# DIOT_PSU_integrated.net
KiCad netlist of a schematic drawn in Altium Designer
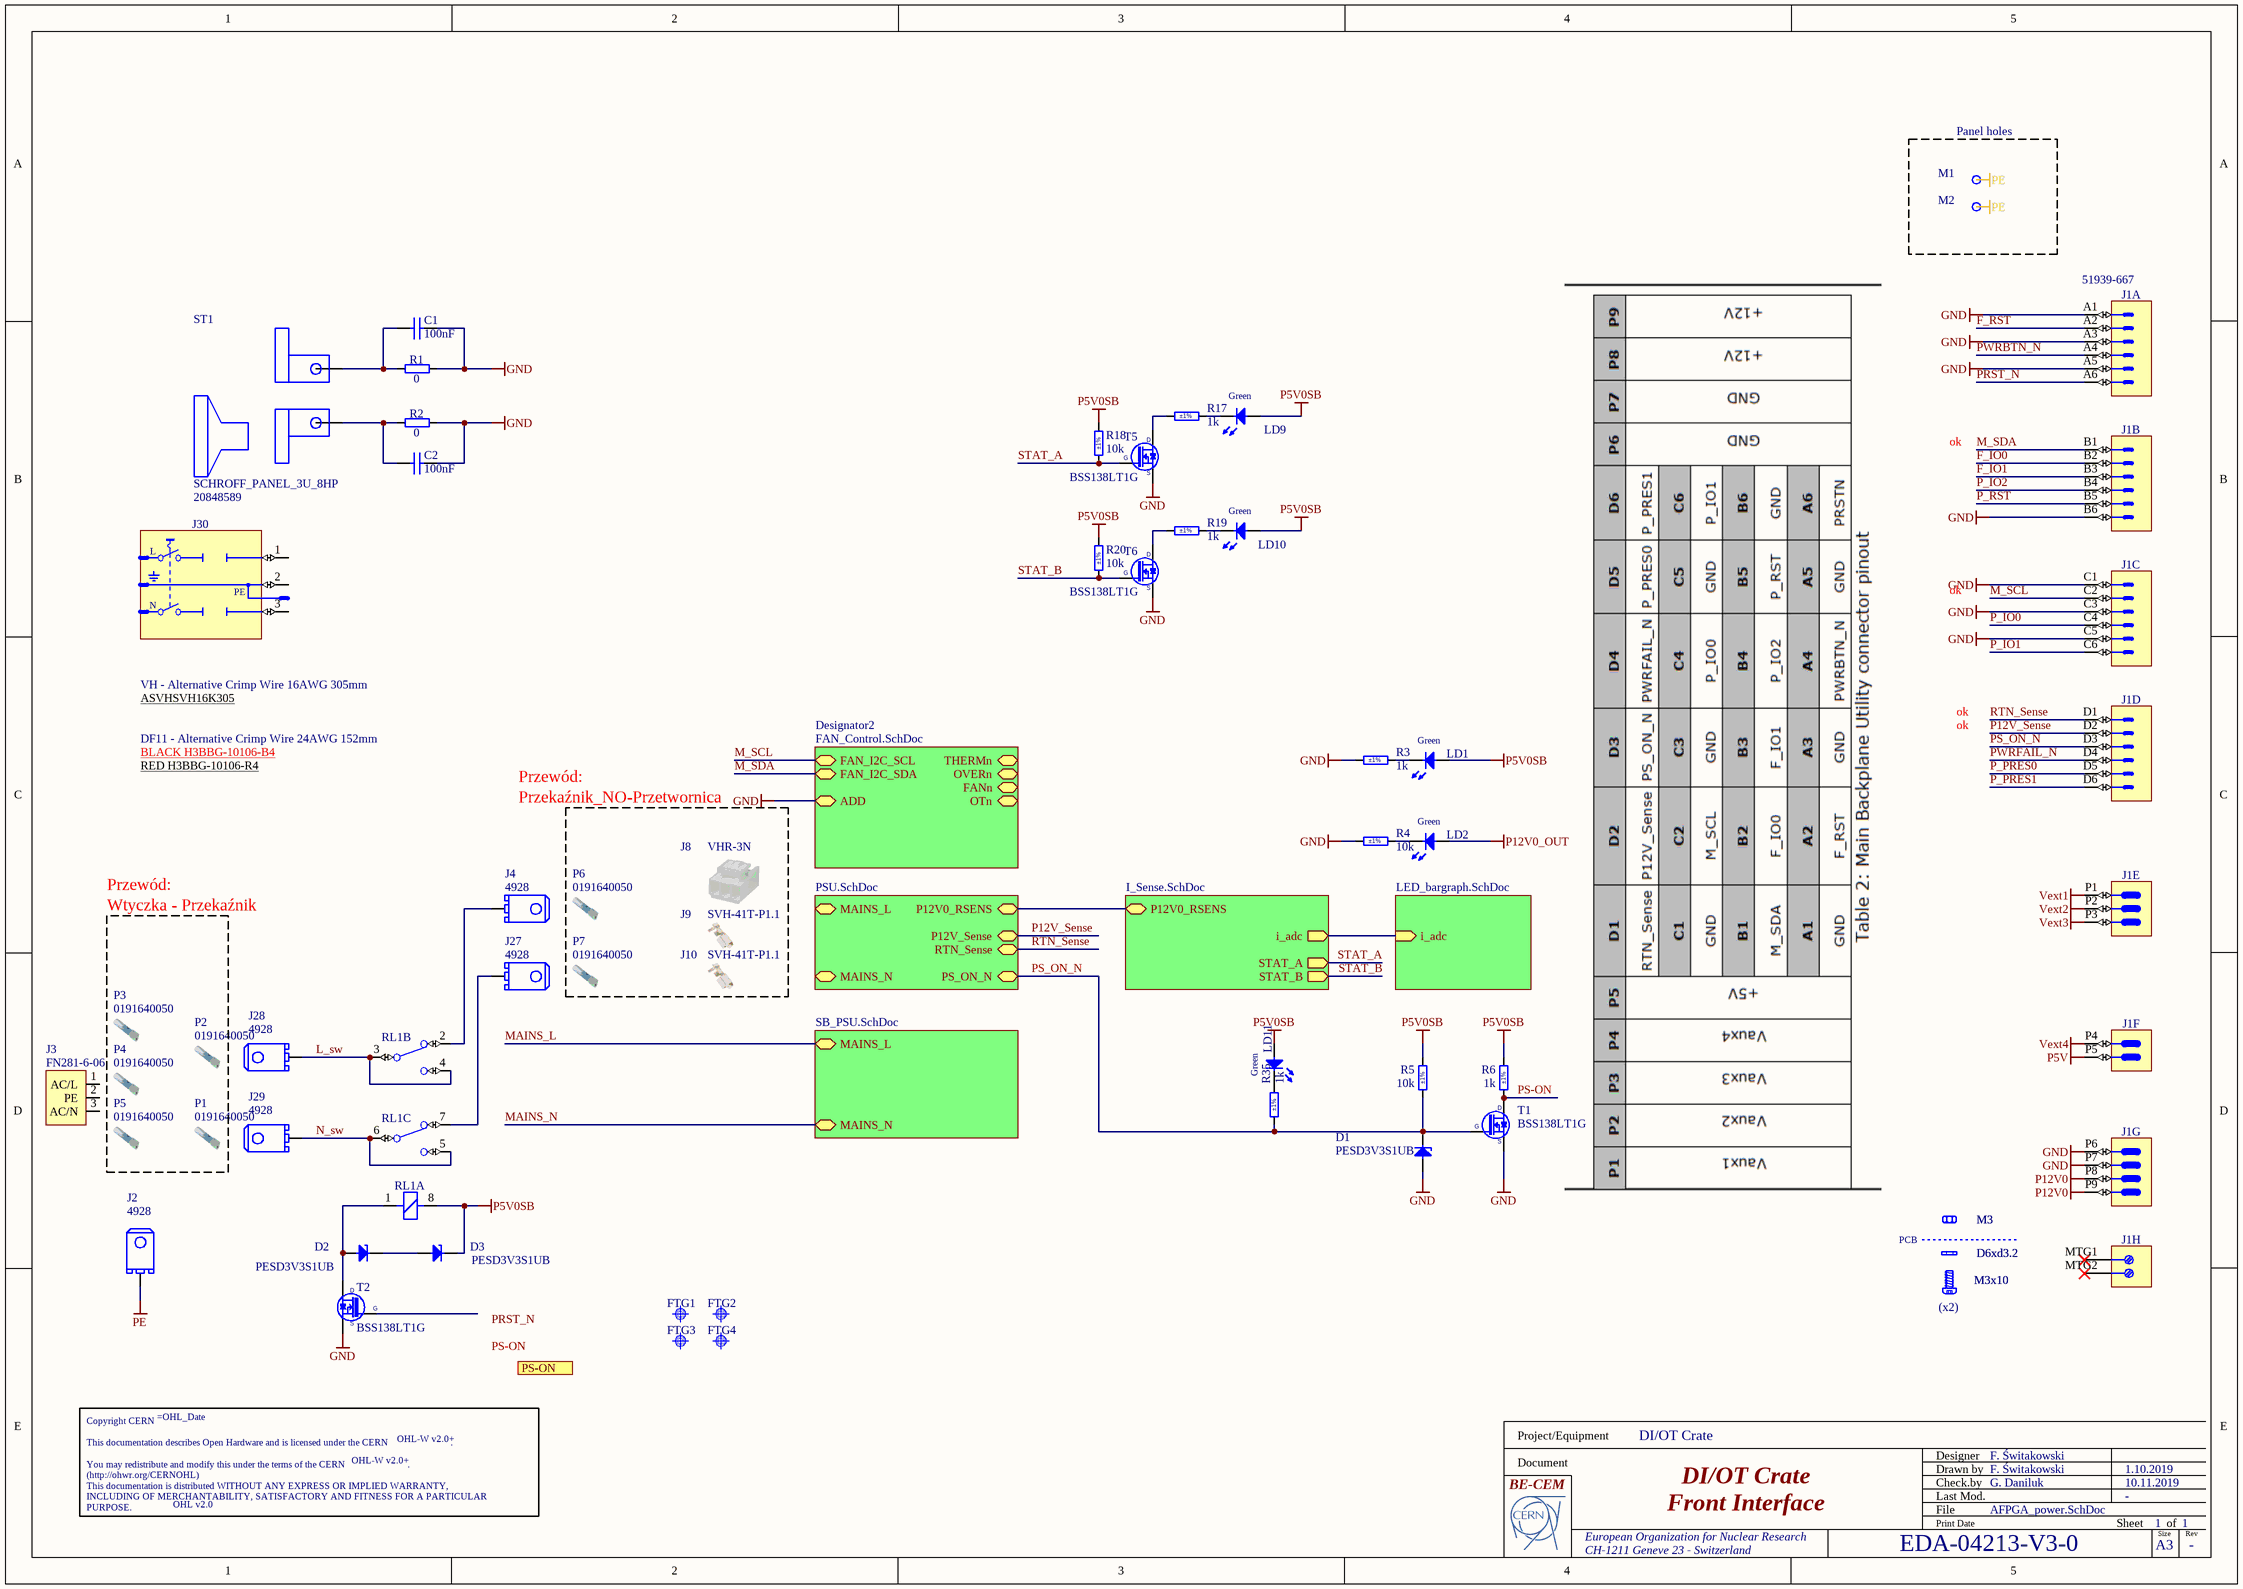
[diagram p0: DIOT_PSU_integrated.SchDoc]

(export (version "E")
  (design (tool "Eeschema 10.0.6"))
  (components
    (comp (ref "C1")
      (value "100nF")
      (footprint "CAPC1608X87N")
      (description "Non-polarised capacitor")
      (fields
        (field (name "PART NUMBER") "CC0603_100NF_50V_10%_X5R")
        (field (name "VOLTAGE") "50V")
        (field (name "AUTHOR") "CERN DEM MR")
      )
      (libsource (lib "Capacitors") (part "Capacitor - non polarized"))
    )
    (comp (ref "C2")
      (value "100nF")
      (footprint "CAPC1608X87N")
      (description "Non-polarised capacitor")
      (fields
        (field (name "PART NUMBER") "CC0603_100NF_50V_10%_X5R")
        (field (name "VOLTAGE") "50V")
        (field (name "AUTHOR") "CERN DEM MR")
      )
      (libsource (lib "Capacitors") (part "Capacitor - non polarized"))
    )
    (comp (ref "D1")
      (value "PESD3V3S1UB")
      (footprint "SODFL1608X65N")
      (description "ESD protection diode")
      (fields
        (field (name "VOLTAGE") "3V3")
        (field (name "POWER") "330W")
        (field (name "AUTHOR") "CERN DEM JLC")
      )
      (libsource (lib "ICs And Semiconductors") (part "Diode ESD"))
    )
    (comp (ref "D2")
      (value "PESD3V3S1UB")
      (footprint "SODFL1608X65N")
      (description "ESD protection diode")
      (fields
        (field (name "VOLTAGE") "3V3")
        (field (name "POWER") "330W")
        (field (name "AUTHOR") "CERN DEM JLC")
      )
      (libsource (lib "ICs And Semiconductors") (part "Diode ESD"))
    )
    (comp (ref "D3")
      (value "PESD3V3S1UB")
      (footprint "SODFL1608X65N")
      (description "ESD protection diode")
      (fields
        (field (name "VOLTAGE") "3V3")
        (field (name "POWER") "330W")
        (field (name "AUTHOR") "CERN DEM JLC")
      )
      (libsource (lib "ICs And Semiconductors") (part "Diode ESD"))
    )
    (comp (ref "FTG1")
      (value "Use only in PCB")
      (footprint "FIDUCIAL_TOP_C100-200")
      (description "Fiducial Target")
      (fields (field (name "PART NUMBER") "FIDUCIAL_TARGET_C100-200") (field (name "AUTHOR") "CERN DEM JLC"))
      (libsource (lib "Eletro-mechanical") (part "Fiducial Target"))
    )
    (comp (ref "FTG2")
      (value "Use only in PCB")
      (footprint "FIDUCIAL_TOP_S100-200")
      (description "Fiducial Target")
      (fields (field (name "PART NUMBER") "FIDUCIAL_TARGET_S100-200") (field (name "AUTHOR") "CERN DEM JLC"))
      (libsource (lib "Eletro-mechanical") (part "Fiducial Target"))
    )
    (comp (ref "FTG3")
      (value "Use only in PCB")
      (footprint "FIDUCIAL_TOP_C100-200")
      (description "Fiducial Target")
      (fields (field (name "PART NUMBER") "FIDUCIAL_TARGET_C100-200") (field (name "AUTHOR") "CERN DEM JLC"))
      (libsource (lib "Eletro-mechanical") (part "Fiducial Target"))
    )
    (comp (ref "FTG4")
      (value "Use only in PCB")
      (footprint "FIDUCIAL_TOP_S100-200")
      (description "Fiducial Target")
      (fields (field (name "PART NUMBER") "FIDUCIAL_TARGET_S100-200") (field (name "AUTHOR") "CERN DEM JLC"))
      (libsource (lib "Eletro-mechanical") (part "Fiducial Target"))
    )
    (comp (ref "J1")
      (value "PwrBlade")
      (footprint "AMPHENOL_51939-667")
      (description "Thru-Hole, Lead 3.43mm, PowerBlade Right Angled Power Connector 3ACP 2P 24S 4P Contacts")
      (fields
        (field (name "PART NUMBER") "AMPHENOL_51939-667")
        (field (name "MANUFACTURER") "AMPHENOL")
        (field (name "MANUFACTURER PART NUMBER") "51939-667")
        (field (name "AUTHOR") "CERN DEM JLC")
      )
      (libsource (lib "Connectors") (part "AMPHENOL_51939-667"))
    )
    (comp (ref "J2")
      (value "4928")
      (footprint "KEYSTONE_4928")
      (description "0.240\" (6.10mm) Quick Connect Male Solder Connector Non-Insulated")
      (fields (field (name "MANUFACTURER") "KEYSTONE") (field (name "AUTHOR") "LPA"))
      (libsource (lib "DIOT_PSU_integrated") (part "KEYSTONE_4928"))
    )
    (comp (ref "J3")
      (value "FN281-6-06")
      (footprint "FN9264-2-06")
      (description "Power Entry Connector Receptacle, Male Blades - Module IEC 320-C14 Panel Mount, Flange")
      (fields (field (name "MANUFACTURER") "Schaffner EMC Inc.") (field (name "AUTHOR") "LPA"))
      (libsource (lib "DIOT_PSU_integrated") (part "FN281-6-06"))
    )
    (comp (ref "J4")
      (value "4928")
      (footprint "KEYSTONE_4928")
      (description "0.240\" (6.10mm) Quick Connect Male Solder Connector Non-Insulated")
      (fields (field (name "MANUFACTURER") "KEYSTONE") (field (name "AUTHOR") "LPA"))
      (libsource (lib "DIOT_PSU_integrated") (part "KEYSTONE_4928"))
    )
    (comp (ref "J8")
      (value "VHR-3N")
      (footprint "VHR-3N")
      (description "3 Rectangular Connectors - Housings Receptacle Natural 0.156\" (3.96mm)")
      (fields (field (name "MANUFACTURER") "JST Sales America Inc.") (field (name "AUTHOR") "LPA"))
      (libsource (lib "EDA-04213-V3-0_project") (part "VHR-3N"))
    )
    (comp (ref "J9")
      (value "SVH-41T-P1.1")
      (footprint "SVH-41T-P1.1")
      (description "Socket Contact Tin 16-20 AWG Crimp")
      (fields (field (name "MANUFACTURER") "JST Sales America Inc.") (field (name "AUTHOR") "LPA"))
      (libsource (lib "EDA-04213-V3-0_project") (part "SVH-41T-P1.1"))
    )
    (comp (ref "J10")
      (value "SVH-41T-P1.1")
      (footprint "SVH-41T-P1.1")
      (description "Socket Contact Tin 16-20 AWG Crimp")
      (fields (field (name "MANUFACTURER") "JST Sales America Inc.") (field (name "AUTHOR") "LPA"))
      (libsource (lib "EDA-04213-V3-0_project") (part "SVH-41T-P1.1"))
    )
    (comp (ref "J27")
      (value "4928")
      (footprint "KEYSTONE_4928")
      (description "0.240\" (6.10mm) Quick Connect Male Solder Connector Non-Insulated")
      (fields (field (name "MANUFACTURER") "KEYSTONE") (field (name "AUTHOR") "LPA"))
      (libsource (lib "DIOT_PSU_integrated") (part "KEYSTONE_4928"))
    )
    (comp (ref "J28")
      (value "4928")
      (footprint "KEYSTONE_4928")
      (description "0.240\" (6.10mm) Quick Connect Male Solder Connector Non-Insulated")
      (fields (field (name "MANUFACTURER") "KEYSTONE") (field (name "AUTHOR") "LPA"))
      (libsource (lib "DIOT_PSU_integrated") (part "KEYSTONE_4928"))
    )
    (comp (ref "J29")
      (value "4928")
      (footprint "KEYSTONE_4928")
      (description "0.240\" (6.10mm) Quick Connect Male Solder Connector Non-Insulated")
      (fields (field (name "MANUFACTURER") "KEYSTONE") (field (name "AUTHOR") "LPA"))
      (libsource (lib "DIOT_PSU_integrated") (part "KEYSTONE_4928"))
    )
    (comp (ref "J30")
      (value "IEC")
      (footprint "SCHURTER_DD21.0121.1111")
      (description "Connector 3 Male 2P+ 2 Fuse Holder + Line Switch 2 Poles")
      (fields
        (field (name "PART NUMBER") "SCHURTER_DD21.0121.1111")
        (field (name "MANUFACTURER") "SCHURTER")
        (field (name "AUTHOR") "CERN DEM JLC")
      )
      (libsource (lib "Connectors") (part "Connector 3 Male 2P+T+2FUSH+SW2P"))
    )
    (comp (ref "LD1")
      (value "Green")
      (footprint "LED_AVAGO_HSME-C120")
      (description "LED Green 1C 2A")
      (fields
        (field (name "PART NUMBER") "LED_AVAGO_HSME-C120")
        (field (name "MANUFACTURER") "AVAGO TECHNOLOGIES")
        (field (name "AUTHOR") "CERN DEM JMW")
      )
      (libsource (lib "ICs And Semiconductors") (part "LED Green 1C 2A"))
    )
    (comp (ref "LD2")
      (value "Green")
      (footprint "LED_AVAGO_HSME-C120")
      (description "LED Green 1C 2A")
      (fields
        (field (name "PART NUMBER") "LED_AVAGO_HSME-C120")
        (field (name "MANUFACTURER") "AVAGO TECHNOLOGIES")
        (field (name "AUTHOR") "CERN DEM JMW")
      )
      (libsource (lib "ICs And Semiconductors") (part "LED Green 1C 2A"))
    )
    (comp (ref "LD9")
      (value "Green")
      (footprint "LED_AVAGO_HSME-C120")
      (description "LED Green 1C 2A")
      (fields
        (field (name "PART NUMBER") "LED_AVAGO_HSME-C120")
        (field (name "MANUFACTURER") "AVAGO TECHNOLOGIES")
        (field (name "AUTHOR") "CERN DEM JMW")
      )
      (libsource (lib "ICs And Semiconductors") (part "LED Green 1C 2A"))
    )
    (comp (ref "LD10")
      (value "Green")
      (footprint "LED_AVAGO_HSME-C120")
      (description "LED Green 1C 2A")
      (fields
        (field (name "PART NUMBER") "LED_AVAGO_HSME-C120")
        (field (name "MANUFACTURER") "AVAGO TECHNOLOGIES")
        (field (name "AUTHOR") "CERN DEM JMW")
      )
      (libsource (lib "ICs And Semiconductors") (part "LED Green 1C 2A"))
    )
    (comp (ref "LD11")
      (value "Green")
      (footprint "LED_AVAGO_HSME-C120")
      (description "LED Green 1C 2A")
      (fields
        (field (name "PART NUMBER") "LED_AVAGO_HSME-C120")
        (field (name "MANUFACTURER") "AVAGO TECHNOLOGIES")
        (field (name "AUTHOR") "CERN DEM JMW")
      )
      (libsource (lib "ICs And Semiconductors") (part "LED Green 1C 2A"))
    )
    (comp (ref "M1")
      (value "Plated Hole")
      (footprint "MTG300_600")
      (description "Single Terminal Socket")
      (fields (field (name "PART NUMBER") "PLATED_HOLE3.0_PAD6.0") (field (name "AUTHOR") "CERN DEM JLC"))
      (libsource (lib "Eletro-mechanical") (part "Single Terminal Socket"))
    )
    (comp (ref "M2")
      (value "Plated Hole")
      (footprint "MTG300_600")
      (description "Single Terminal Socket")
      (fields (field (name "PART NUMBER") "PLATED_HOLE3.0_PAD6.0") (field (name "AUTHOR") "CERN DEM JLC"))
      (libsource (lib "Eletro-mechanical") (part "Single Terminal Socket"))
    )
    (comp (ref "NUT1")
      (value "M3")
      (footprint "BOSSARD_BN628-1241443_v")
      (description "Nut")
      (fields
        (field (name "PART NUMBER") "BOSSARD_BN628-1241443_v")
        (field (name "MANUFACTURER") "BOSSARD")
        (field (name "AUTHOR") "CERN DEM JMW")
      )
      (libsource (lib "Eletro-mechanical") (part "Nut"))
    )
    (comp (ref "NUT2")
      (value "M3")
      (footprint "BOSSARD_BN628-1241443_v")
      (description "Nut")
      (fields
        (field (name "PART NUMBER") "BOSSARD_BN628-1241443_v")
        (field (name "MANUFACTURER") "BOSSARD")
        (field (name "AUTHOR") "CERN DEM JMW")
      )
      (libsource (lib "Eletro-mechanical") (part "Nut"))
    )
    (comp (ref "OHL1")
      (value "CERN_OHL")
      (footprint "CERN_OHL")
      (fields (field (name "AUTHOR") "CERN DEM HF"))
      (libsource (lib "Eletro-mechanical") (part "CERN_OHL"))
    )
    (comp (ref "P1")
      (value "0191640050")
      (footprint "0191640050")
      (description "0.250\" (6.35mm) Quick Connect Female 14-16 AWG Crimp Connector Fully Insulated Heat Shrink")
      (fields (field (name "MANUFACTURER") "Molex") (field (name "AUTHOR") "LPA"))
      (libsource (lib "EDA-04213-V3-0_project") (part "0191640050"))
    )
    (comp (ref "P2")
      (value "0191640050")
      (footprint "0191640050")
      (description "0.250\" (6.35mm) Quick Connect Female 14-16 AWG Crimp Connector Fully Insulated Heat Shrink")
      (fields (field (name "MANUFACTURER") "Molex") (field (name "AUTHOR") "LPA"))
      (libsource (lib "EDA-04213-V3-0_project") (part "0191640050"))
    )
    (comp (ref "P3")
      (value "0191640050")
      (footprint "0191640050")
      (description "0.250\" (6.35mm) Quick Connect Female 14-16 AWG Crimp Connector Fully Insulated Heat Shrink")
      (fields (field (name "MANUFACTURER") "Molex") (field (name "AUTHOR") "LPA"))
      (libsource (lib "EDA-04213-V3-0_project") (part "0191640050"))
    )
    (comp (ref "P4")
      (value "0191640050")
      (footprint "0191640050")
      (description "0.250\" (6.35mm) Quick Connect Female 14-16 AWG Crimp Connector Fully Insulated Heat Shrink")
      (fields (field (name "MANUFACTURER") "Molex") (field (name "AUTHOR") "LPA"))
      (libsource (lib "EDA-04213-V3-0_project") (part "0191640050"))
    )
    (comp (ref "P5")
      (value "0191640050")
      (footprint "0191640050")
      (description "0.250\" (6.35mm) Quick Connect Female 14-16 AWG Crimp Connector Fully Insulated Heat Shrink")
      (fields (field (name "MANUFACTURER") "Molex") (field (name "AUTHOR") "LPA"))
      (libsource (lib "EDA-04213-V3-0_project") (part "0191640050"))
    )
    (comp (ref "P6")
      (value "0191640050")
      (footprint "0191640050")
      (description "0.250\" (6.35mm) Quick Connect Female 14-16 AWG Crimp Connector Fully Insulated Heat Shrink")
      (fields (field (name "MANUFACTURER") "Molex") (field (name "AUTHOR") "LPA"))
      (libsource (lib "EDA-04213-V3-0_project") (part "0191640050"))
    )
    (comp (ref "P7")
      (value "0191640050")
      (footprint "0191640050")
      (description "0.250\" (6.35mm) Quick Connect Female 14-16 AWG Crimp Connector Fully Insulated Heat Shrink")
      (fields (field (name "MANUFACTURER") "Molex") (field (name "AUTHOR") "LPA"))
      (libsource (lib "EDA-04213-V3-0_project") (part "0191640050"))
    )
    (comp (ref "R1")
      (value "0")
      (footprint "RESC1608X55N")
      (description "Resistor")
      (fields
        (field (name "PART NUMBER") "R0603_0R_JUMPER")
        (field (name "MANUFACTURER") "GENERIC")
        (field (name "AUTHOR") "CERN DEM JLC")
      )
      (libsource (lib "Resistors") (part "Resistor"))
    )
    (comp (ref "R2")
      (value "0")
      (footprint "RESC1608X55N")
      (description "Resistor")
      (fields
        (field (name "PART NUMBER") "R0603_0R_JUMPER")
        (field (name "MANUFACTURER") "GENERIC")
        (field (name "AUTHOR") "CERN DEM JLC")
      )
      (libsource (lib "Resistors") (part "Resistor"))
    )
    (comp (ref "R3")
      (value "1k")
      (footprint "RESC1608X55N")
      (description "Resistor - 1%")
      (fields
        (field (name "TOLERANCE") "±1%")
        (field (name "PART NUMBER") "R0603_1K_1%_0.1W_100PPM")
        (field (name "POWER") "0.1W")
        (field (name "AUTHOR") "CERN DEM JLC")
      )
      (libsource (lib "Resistors") (part "Resistor - 1%"))
    )
    (comp (ref "R4")
      (value "10k")
      (footprint "RESC1608X55N")
      (description "Resistor - 1%")
      (fields
        (field (name "TOLERANCE") "±1%")
        (field (name "PART NUMBER") "R0603_10K_1%_0.1W_100PPM")
        (field (name "POWER") "0.1W")
        (field (name "AUTHOR") "CERN DEM JLC")
      )
      (libsource (lib "Resistors") (part "Resistor - 1%"))
    )
    (comp (ref "R5")
      (value "10k")
      (footprint "RESC1608X55N")
      (description "Resistor - 1%")
      (fields
        (field (name "TOLERANCE") "±1%")
        (field (name "PART NUMBER") "R0603_10K_1%_0.1W_100PPM")
        (field (name "POWER") "0.1W")
        (field (name "AUTHOR") "CERN DEM JLC")
      )
      (libsource (lib "Resistors") (part "Resistor - 1%"))
    )
    (comp (ref "R6")
      (value "1k")
      (footprint "RESC1608X55N")
      (description "Resistor - 1%")
      (fields
        (field (name "TOLERANCE") "±1%")
        (field (name "PART NUMBER") "R0603_1K_1%_0.1W_100PPM")
        (field (name "POWER") "0.1W")
        (field (name "AUTHOR") "CERN DEM JLC")
      )
      (libsource (lib "Resistors") (part "Resistor - 1%"))
    )
    (comp (ref "R17")
      (value "1k")
      (footprint "RESC1608X55N")
      (description "Resistor - 1%")
      (fields
        (field (name "TOLERANCE") "±1%")
        (field (name "PART NUMBER") "R0603_1K_1%_0.1W_100PPM")
        (field (name "POWER") "0.1W")
        (field (name "AUTHOR") "CERN DEM JLC")
      )
      (libsource (lib "Resistors") (part "Resistor - 1%"))
    )
    (comp (ref "R18")
      (value "10k")
      (footprint "RESC1608X55N")
      (description "Resistor - 1%")
      (fields
        (field (name "TOLERANCE") "±1%")
        (field (name "PART NUMBER") "R0603_10K_1%_0.1W_100PPM")
        (field (name "POWER") "0.1W")
        (field (name "AUTHOR") "CERN DEM JLC")
      )
      (libsource (lib "Resistors") (part "Resistor - 1%"))
    )
    (comp (ref "R19")
      (value "1k")
      (footprint "RESC1608X55N")
      (description "Resistor - 1%")
      (fields
        (field (name "TOLERANCE") "±1%")
        (field (name "PART NUMBER") "R0603_1K_1%_0.1W_100PPM")
        (field (name "POWER") "0.1W")
        (field (name "AUTHOR") "CERN DEM JLC")
      )
      (libsource (lib "Resistors") (part "Resistor - 1%"))
    )
    (comp (ref "R20")
      (value "10k")
      (footprint "RESC1608X55N")
      (description "Resistor - 1%")
      (fields
        (field (name "TOLERANCE") "±1%")
        (field (name "PART NUMBER") "R0603_10K_1%_0.1W_100PPM")
        (field (name "POWER") "0.1W")
        (field (name "AUTHOR") "CERN DEM JLC")
      )
      (libsource (lib "Resistors") (part "Resistor - 1%"))
    )
    (comp (ref "R35")
      (value "1k")
      (footprint "RESC1608X55N")
      (description "Resistor - 1%")
      (fields
        (field (name "TOLERANCE") "±1%")
        (field (name "PART NUMBER") "R0603_1K_1%_0.1W_100PPM")
        (field (name "POWER") "0.1W")
        (field (name "AUTHOR") "CERN DEM JLC")
      )
      (libsource (lib "Resistors") (part "Resistor - 1%"))
    )
    (comp (ref "RL1")
      (value "REL_OMRON_G2RL-24")
      (footprint "REL_OMRON_G2RL-24")
      (description "DPDT Power Relay, G2RL Series")
      (fields
        (field (name "PART NUMBER") "REL_OMRON_G2RL-24-DC5")
        (field (name "MANUFACTURER") "OMRON ELECTRONIC")
        (field (name "AUTHOR") "CERN DEM BC")
      )
      (libsource (lib "Eletro-mechanical") (part "REL_OMRON_G2RL-24"))
    )
    (comp (ref "SCREW1")
      (value "M3x10")
      (footprint "BOSSARD_BN5687-3061608_v")
      (description "Screw")
      (fields
        (field (name "PART NUMBER") "BOSSARD_BN5687-3061608_v")
        (field (name "MANUFACTURER") "BOSSARD")
        (field (name "AUTHOR") "CERN DEM JLC")
      )
      (libsource (lib "Eletro-mechanical") (part "Screw"))
    )
    (comp (ref "SCREW2")
      (value "M3x10")
      (footprint "BOSSARD_BN5687-3061608_v")
      (description "Screw")
      (fields
        (field (name "PART NUMBER") "BOSSARD_BN5687-3061608_v")
        (field (name "MANUFACTURER") "BOSSARD")
        (field (name "AUTHOR") "CERN DEM JLC")
      )
      (libsource (lib "Eletro-mechanical") (part "Screw"))
    )
    (comp (ref "ST1")
      (value "SCHROFF_PANEL_3U_8HP")
      (footprint "SCHROFF_PANEL_3HP_8U_CPCIS_AC_PSU")
      (description "Schroff 8HP 4U EUROCARD Panel with ejector")
      (fields
        (field (name "MANUFACTURER") "Schroff")
        (field (name "MANUFACTURER PART NUMBER") "20848589")
        (field (name "MANUFACTURER PART NUMBER 2") "20848589")
      )
      (libsource (lib "DIOT_PSU_integrated") (part "SCHROFF_PANEL_3U_8HP_CPCIS_PSU"))
    )
    (comp (ref "T1")
      (value "BSS138LT1G")
      (footprint "SOT95P240X110-3N")
      (description "N-CHANNEL MOSFET WITH DIODE")
      (fields
        (field (name "MANUFACTURER") "ON SEMICONDUCTOR")
        (field (name "MANUFACTURER PART NUMBER") "BSS138L")
        (field (name "AUTHOR") "CERN DEM JLC")
      )
      (libsource (lib "ICs And Semiconductors") (part "N-MOSFET-D 1G 2S 3D"))
    )
    (comp (ref "T2")
      (value "BSS138LT1G")
      (footprint "SOT95P240X110-3N")
      (description "N-CHANNEL MOSFET WITH DIODE")
      (fields
        (field (name "MANUFACTURER") "ON SEMICONDUCTOR")
        (field (name "MANUFACTURER PART NUMBER") "BSS138L")
        (field (name "AUTHOR") "CERN DEM JLC")
      )
      (libsource (lib "") (part "N-MOSFET-D 1G 2S 3D_1"))
    )
    (comp (ref "T5")
      (value "BSS138LT1G")
      (footprint "SOT95P240X110-3N")
      (description "N-CHANNEL MOSFET WITH DIODE")
      (fields (field (name "MANUFACTURER") "ON SEMICONDUCTOR") (field (name "AUTHOR") "CERN DEM JLC"))
      (libsource (lib "ICs And Semiconductors") (part "N-MOSFET-D 1G 2S 3D"))
    )
    (comp (ref "T6")
      (value "BSS138LT1G")
      (footprint "SOT95P240X110-3N")
      (description "N-CHANNEL MOSFET WITH DIODE")
      (fields (field (name "MANUFACTURER") "ON SEMICONDUCTOR") (field (name "AUTHOR") "CERN DEM JLC"))
      (libsource (lib "ICs And Semiconductors") (part "N-MOSFET-D 1G 2S 3D"))
    )
    (comp (ref "WASHER1")
      (value "D6xd3.2")
      (footprint "BOSSARD_BN83728-8243964_v")
      (description "Washer")
      (fields
        (field (name "PART NUMBER") "BOSSARD_BN83728-8243964_v")
        (field (name "MANUFACTURER") "BOSSARD")
        (field (name "AUTHOR") "CERN DEM JLC")
      )
      (libsource (lib "Eletro-mechanical") (part "Washer"))
    )
    (comp (ref "WASHER2")
      (value "D6xd3.2")
      (footprint "BOSSARD_BN83728-8243964_v")
      (description "Washer")
      (fields
        (field (name "PART NUMBER") "BOSSARD_BN83728-8243964_v")
        (field (name "MANUFACTURER") "BOSSARD")
        (field (name "AUTHOR") "CERN DEM JLC")
      )
      (libsource (lib "Eletro-mechanical") (part "Washer"))
    )
  )
  (nets
    (net (code "2") (name "/F_IO0") (class "Default")
      (node (ref "J1") (pin "B2") (pinfunction "B2_B2") (pintype "bidirectional"))
    )
    (net (code "3") (name "/F_IO1") (class "Default")
      (node (ref "J1") (pin "B3") (pinfunction "B3_B3") (pintype "bidirectional"))
    )
    (net (code "4") (name "/F_RST") (class "Default")
      (node (ref "J1") (pin "A2") (pinfunction "A2_A2") (pintype "bidirectional"))
    )
    (net (code "5") (name "/L_sw") (class "Default")
      (node (ref "J28") (pin "1") (pinfunction "1_1") (pintype "passive"))
      (node (ref "RL1") (pin "3") (pinfunction "C_3") (pintype "bidirectional"))
      (node (ref "RL1") (pin "4") (pinfunction "NO_4") (pintype "bidirectional"))
    )
    (net (code "10") (name "/M_SCL") (class "Default")
      (node (ref "J1") (pin "C2") (pinfunction "C2_C2") (pintype "bidirectional"))
    )
    (net (code "11") (name "/M_SDA") (class "Default")
      (node (ref "J1") (pin "B1") (pinfunction "B1_B1") (pintype "bidirectional"))
    )
    (net (code "12") (name "/N_sw") (class "Default")
      (node (ref "J29") (pin "1") (pinfunction "1_1") (pintype "passive"))
      (node (ref "RL1") (pin "5") (pinfunction "NO_5") (pintype "bidirectional"))
      (node (ref "RL1") (pin "6") (pinfunction "C_6") (pintype "bidirectional"))
    )
    (net (code "16") (name "/P12V_Sense") (class "Default")
      (node (ref "J1") (pin "D2") (pinfunction "D2_D2") (pintype "bidirectional"))
    )
    (net (code "17") (name "/PRST_N") (class "Default")
      (node (ref "J1") (pin "A6") (pinfunction "A6_A6") (pintype "bidirectional"))
    )
    (net (code "18") (name "/PS-ON") (class "Default")
      (node (ref "R6") (pin "1") (pinfunction "1_1") (pintype "passive"))
      (node (ref "T1") (pin "3") (pinfunction "D_3") (pintype "passive"))
    )
    (net (code "19") (name "/PS_ON_N") (class "Default")
      (node (ref "D1") (pin "1") (pinfunction "C_1") (pintype "passive"))
      (node (ref "J1") (pin "D3") (pinfunction "D3_D3") (pintype "bidirectional"))
      (node (ref "R35") (pin "1") (pinfunction "1_1") (pintype "passive"))
      (node (ref "R5") (pin "1") (pinfunction "1_1") (pintype "passive"))
      (node (ref "T1") (pin "1") (pinfunction "G_1") (pintype "passive"))
    )
    (net (code "20") (name "/PWRBTN_N") (class "Default")
      (node (ref "J1") (pin "A4") (pinfunction "A4_A4") (pintype "bidirectional"))
    )
    (net (code "21") (name "/PWRFAIL_N") (class "Default")
      (node (ref "J1") (pin "D4") (pinfunction "D4_D4") (pintype "bidirectional"))
    )
    (net (code "22") (name "/P_IO0") (class "Default")
      (node (ref "J1") (pin "C4") (pinfunction "C4_C4") (pintype "bidirectional"))
    )
    (net (code "23") (name "/P_IO1") (class "Default")
      (node (ref "J1") (pin "C6") (pinfunction "C6_C6") (pintype "bidirectional"))
    )
    (net (code "24") (name "/P_IO2") (class "Default")
      (node (ref "J1") (pin "B4") (pinfunction "B4_B4") (pintype "bidirectional"))
    )
    (net (code "25") (name "/P_PRES0") (class "Default")
      (node (ref "J1") (pin "D5") (pinfunction "D5_D5") (pintype "bidirectional"))
    )
    (net (code "26") (name "/P_PRES1") (class "Default")
      (node (ref "J1") (pin "D6") (pinfunction "D6_D6") (pintype "bidirectional"))
    )
    (net (code "27") (name "/P_RST") (class "Default")
      (node (ref "J1") (pin "B5") (pinfunction "B5_B5") (pintype "bidirectional"))
    )
    (net (code "28") (name "/RTN_Sense") (class "Default")
      (node (ref "J1") (pin "D1") (pinfunction "D1_D1") (pintype "bidirectional"))
    )
    (net (code "29") (name "/STAT_A") (class "Default")
      (node (ref "R18") (pin "1") (pinfunction "1_1") (pintype "passive"))
      (node (ref "T5") (pin "1") (pinfunction "G_1") (pintype "passive"))
    )
    (net (code "30") (name "/STAT_B") (class "Default")
      (node (ref "R20") (pin "1") (pinfunction "1_1") (pintype "passive"))
      (node (ref "T6") (pin "1") (pinfunction "G_1") (pintype "passive"))
    )
    (net (code "33") (name "GND") (class "Default")
      (node (ref "C1") (pin "1") (pinfunction "1_1") (pintype "passive"))
      (node (ref "C2") (pin "1") (pinfunction "1_1") (pintype "passive"))
      (node (ref "D1") (pin "2") (pinfunction "A_2") (pintype "passive"))
      (node (ref "J1") (pin "A1") (pinfunction "A1_A1") (pintype "bidirectional"))
      (node (ref "J1") (pin "A3") (pinfunction "A3_A3") (pintype "bidirectional"))
      (node (ref "J1") (pin "A5") (pinfunction "A5_A5") (pintype "bidirectional"))
      (node (ref "J1") (pin "B6") (pinfunction "B6_B6") (pintype "bidirectional"))
      (node (ref "J1") (pin "C1") (pinfunction "C1_C1") (pintype "bidirectional"))
      (node (ref "J1") (pin "C3") (pinfunction "C3_C3") (pintype "bidirectional"))
      (node (ref "J1") (pin "C5") (pinfunction "C5_C5") (pintype "bidirectional"))
      (node (ref "J1") (pin "P6") (pinfunction "P6_P6") (pintype "bidirectional"))
      (node (ref "J1") (pin "P7") (pinfunction "P7_P7") (pintype "bidirectional"))
      (node (ref "R1") (pin "2") (pinfunction "2_2") (pintype "passive"))
      (node (ref "R2") (pin "2") (pinfunction "2_2") (pintype "passive"))
      (node (ref "R3") (pin "1") (pinfunction "1_1") (pintype "passive"))
      (node (ref "R4") (pin "1") (pinfunction "1_1") (pintype "passive"))
      (node (ref "T1") (pin "2") (pinfunction "S_2") (pintype "passive"))
      (node (ref "T2") (pin "2") (pinfunction "S_2") (pintype "passive"))
      (node (ref "T5") (pin "2") (pinfunction "S_2") (pintype "passive"))
      (node (ref "T6") (pin "2") (pinfunction "S_2") (pintype "passive"))
    )
    (net (code "34") (name "Net-(C1-Pad2)") (class "Default")
      (node (ref "C1") (pin "2") (pinfunction "2_2") (pintype "passive"))
      (node (ref "R1") (pin "1") (pinfunction "1_1") (pintype "passive"))
      (node (ref "ST1") (pin "MH1") (pinfunction "MH1_MH1") (pintype "passive"))
    )
    (net (code "35") (name "Net-(C2-Pad2)") (class "Default")
      (node (ref "C2") (pin "2") (pinfunction "2_2") (pintype "passive"))
      (node (ref "R2") (pin "1") (pinfunction "1_1") (pintype "passive"))
      (node (ref "ST1") (pin "MH2") (pinfunction "MH2_MH2") (pintype "passive"))
    )
    (net (code "36") (name "Net-(D2-A)") (class "Default")
      (node (ref "D2") (pin "2") (pinfunction "A_2") (pintype "passive"))
      (node (ref "RL1") (pin "1") (pinfunction "1_1") (pintype "passive"))
      (node (ref "T2") (pin "3") (pinfunction "D_3") (pintype "passive"))
    )
    (net (code "37") (name "Net-(D2-C)") (class "Default")
      (node (ref "D2") (pin "1") (pinfunction "C_1") (pintype "passive"))
      (node (ref "D3") (pin "2") (pinfunction "A_2") (pintype "passive"))
    )
    (net (code "38") (name "Net-(LD1-C)") (class "Default")
      (node (ref "LD1") (pin "1") (pinfunction "C_1") (pintype "passive"))
      (node (ref "R3") (pin "2") (pinfunction "2_2") (pintype "passive"))
    )
    (net (code "39") (name "Net-(LD2-C)") (class "Default")
      (node (ref "LD2") (pin "1") (pinfunction "C_1") (pintype "passive"))
      (node (ref "R4") (pin "2") (pinfunction "2_2") (pintype "passive"))
    )
    (net (code "40") (name "Net-(LD9-C)") (class "Default")
      (node (ref "LD9") (pin "1") (pinfunction "C_1") (pintype "passive"))
      (node (ref "R17") (pin "2") (pinfunction "2_2") (pintype "passive"))
    )
    (net (code "41") (name "Net-(LD10-C)") (class "Default")
      (node (ref "LD10") (pin "1") (pinfunction "C_1") (pintype "passive"))
      (node (ref "R19") (pin "2") (pinfunction "2_2") (pintype "passive"))
    )
    (net (code "42") (name "Net-(LD11-C)") (class "Default")
      (node (ref "LD11") (pin "1") (pinfunction "C_1") (pintype "passive"))
      (node (ref "R35") (pin "2") (pinfunction "2_2") (pintype "passive"))
    )
    (net (code "43") (name "Net-(RL1B-NC)") (class "Default")
      (node (ref "J4") (pin "1") (pinfunction "1_1") (pintype "passive"))
      (node (ref "RL1") (pin "2") (pinfunction "NC_2") (pintype "bidirectional"))
    )
    (net (code "44") (name "Net-(RL1C-NC)") (class "Default")
      (node (ref "J27") (pin "1") (pinfunction "1_1") (pintype "passive"))
      (node (ref "RL1") (pin "7") (pinfunction "NC_7") (pintype "bidirectional"))
    )
    (net (code "45") (name "Net-(T5-D)") (class "Default")
      (node (ref "R17") (pin "1") (pinfunction "1_1") (pintype "passive"))
      (node (ref "T5") (pin "3") (pinfunction "D_3") (pintype "passive"))
    )
    (net (code "46") (name "Net-(T6-D)") (class "Default")
      (node (ref "R19") (pin "1") (pinfunction "1_1") (pintype "passive"))
      (node (ref "T6") (pin "3") (pinfunction "D_3") (pintype "passive"))
    )
    (net (code "47") (name "P5V") (class "Default")
      (node (ref "J1") (pin "P5") (pinfunction "P5_P5") (pintype "bidirectional"))
    )
    (net (code "48") (name "P5V0SB") (class "Default")
      (node (ref "D3") (pin "1") (pinfunction "C_1") (pintype "passive"))
      (node (ref "LD1") (pin "2") (pinfunction "A_2") (pintype "passive"))
      (node (ref "LD10") (pin "2") (pinfunction "A_2") (pintype "passive"))
      (node (ref "LD11") (pin "2") (pinfunction "A_2") (pintype "passive"))
      (node (ref "LD9") (pin "2") (pinfunction "A_2") (pintype "passive"))
      (node (ref "R18") (pin "2") (pinfunction "2_2") (pintype "passive"))
      (node (ref "R20") (pin "2") (pinfunction "2_2") (pintype "passive"))
      (node (ref "R5") (pin "2") (pinfunction "2_2") (pintype "passive"))
      (node (ref "R6") (pin "2") (pinfunction "2_2") (pintype "passive"))
      (node (ref "RL1") (pin "8") (pinfunction "8_8") (pintype "passive"))
    )
    (net (code "49") (name "P12V0") (class "Default")
      (node (ref "J1") (pin "P8") (pinfunction "P8_P8") (pintype "bidirectional"))
      (node (ref "J1") (pin "P9") (pinfunction "P9_P9") (pintype "bidirectional"))
    )
    (net (code "50") (name "P12V0_OUT") (class "Default")
      (node (ref "LD2") (pin "2") (pinfunction "A_2") (pintype "passive"))
    )
    (net (code "51") (name "PE") (class "Default")
      (node (ref "J2") (pin "1") (pinfunction "1_1") (pintype "passive"))
      (node (ref "M1") (pin "1") (pinfunction "1_1") (pintype "bidirectional"))
      (node (ref "M2") (pin "1") (pinfunction "1_1") (pintype "bidirectional"))
    )
    (net (code "52") (name "Vext1") (class "Default")
      (node (ref "J1") (pin "P1") (pinfunction "P1_P1") (pintype "bidirectional"))
    )
    (net (code "53") (name "Vext2") (class "Default")
      (node (ref "J1") (pin "P2") (pinfunction "P2_P2") (pintype "bidirectional"))
    )
    (net (code "54") (name "Vext3") (class "Default")
      (node (ref "J1") (pin "P3") (pinfunction "P3_P3") (pintype "bidirectional"))
    )
    (net (code "55") (name "Vext4") (class "Default")
      (node (ref "J1") (pin "P4") (pinfunction "P4_P4") (pintype "bidirectional"))
    )
    (net (code "56") (name "unconnected-(J1-PadMTG1)") (class "Default")
      (node (ref "J1") (pin "MTG1") (pinfunction "MTG1_MTG1") (pintype "passive+no_connect"))
    )
    (net (code "57") (name "unconnected-(J1-PadMTG2)") (class "Default")
      (node (ref "J1") (pin "MTG2") (pinfunction "MTG2_MTG2") (pintype "passive+no_connect"))
    )
    (net (code "58") (name "unconnected-(J3-AC{slash}L-Pad1)") (class "Default")
      (node (ref "J3") (pin "1") (pinfunction "AC/L_1") (pintype "passive"))
    )
    (net (code "59") (name "unconnected-(J3-AC{slash}N-Pad3)") (class "Default")
      (node (ref "J3") (pin "3") (pinfunction "AC/N_3") (pintype "passive"))
    )
    (net (code "60") (name "unconnected-(J3-PE-Pad2)") (class "Default")
      (node (ref "J3") (pin "2") (pinfunction "PE_2") (pintype "passive"))
    )
    (net (code "61") (name "unconnected-(J30-Pad1)") (class "Default")
      (node (ref "J30") (pin "1") (pinfunction "1_1") (pintype "bidirectional"))
    )
    (net (code "62") (name "unconnected-(J30-Pad2)") (class "Default")
      (node (ref "J30") (pin "2") (pinfunction "2_2") (pintype "bidirectional"))
    )
    (net (code "63") (name "unconnected-(J30-Pad3)") (class "Default")
      (node (ref "J30") (pin "3") (pinfunction "3_3") (pintype "bidirectional"))
    )
    (net (code "64") (name "unconnected-(T2-G-Pad1)") (class "Default")
      (node (ref "T2") (pin "1") (pinfunction "G_1") (pintype "passive"))
    )
  )
)
